# Puissance_proc.net
KiCad netlist of a schematic drawn in Altium Designer
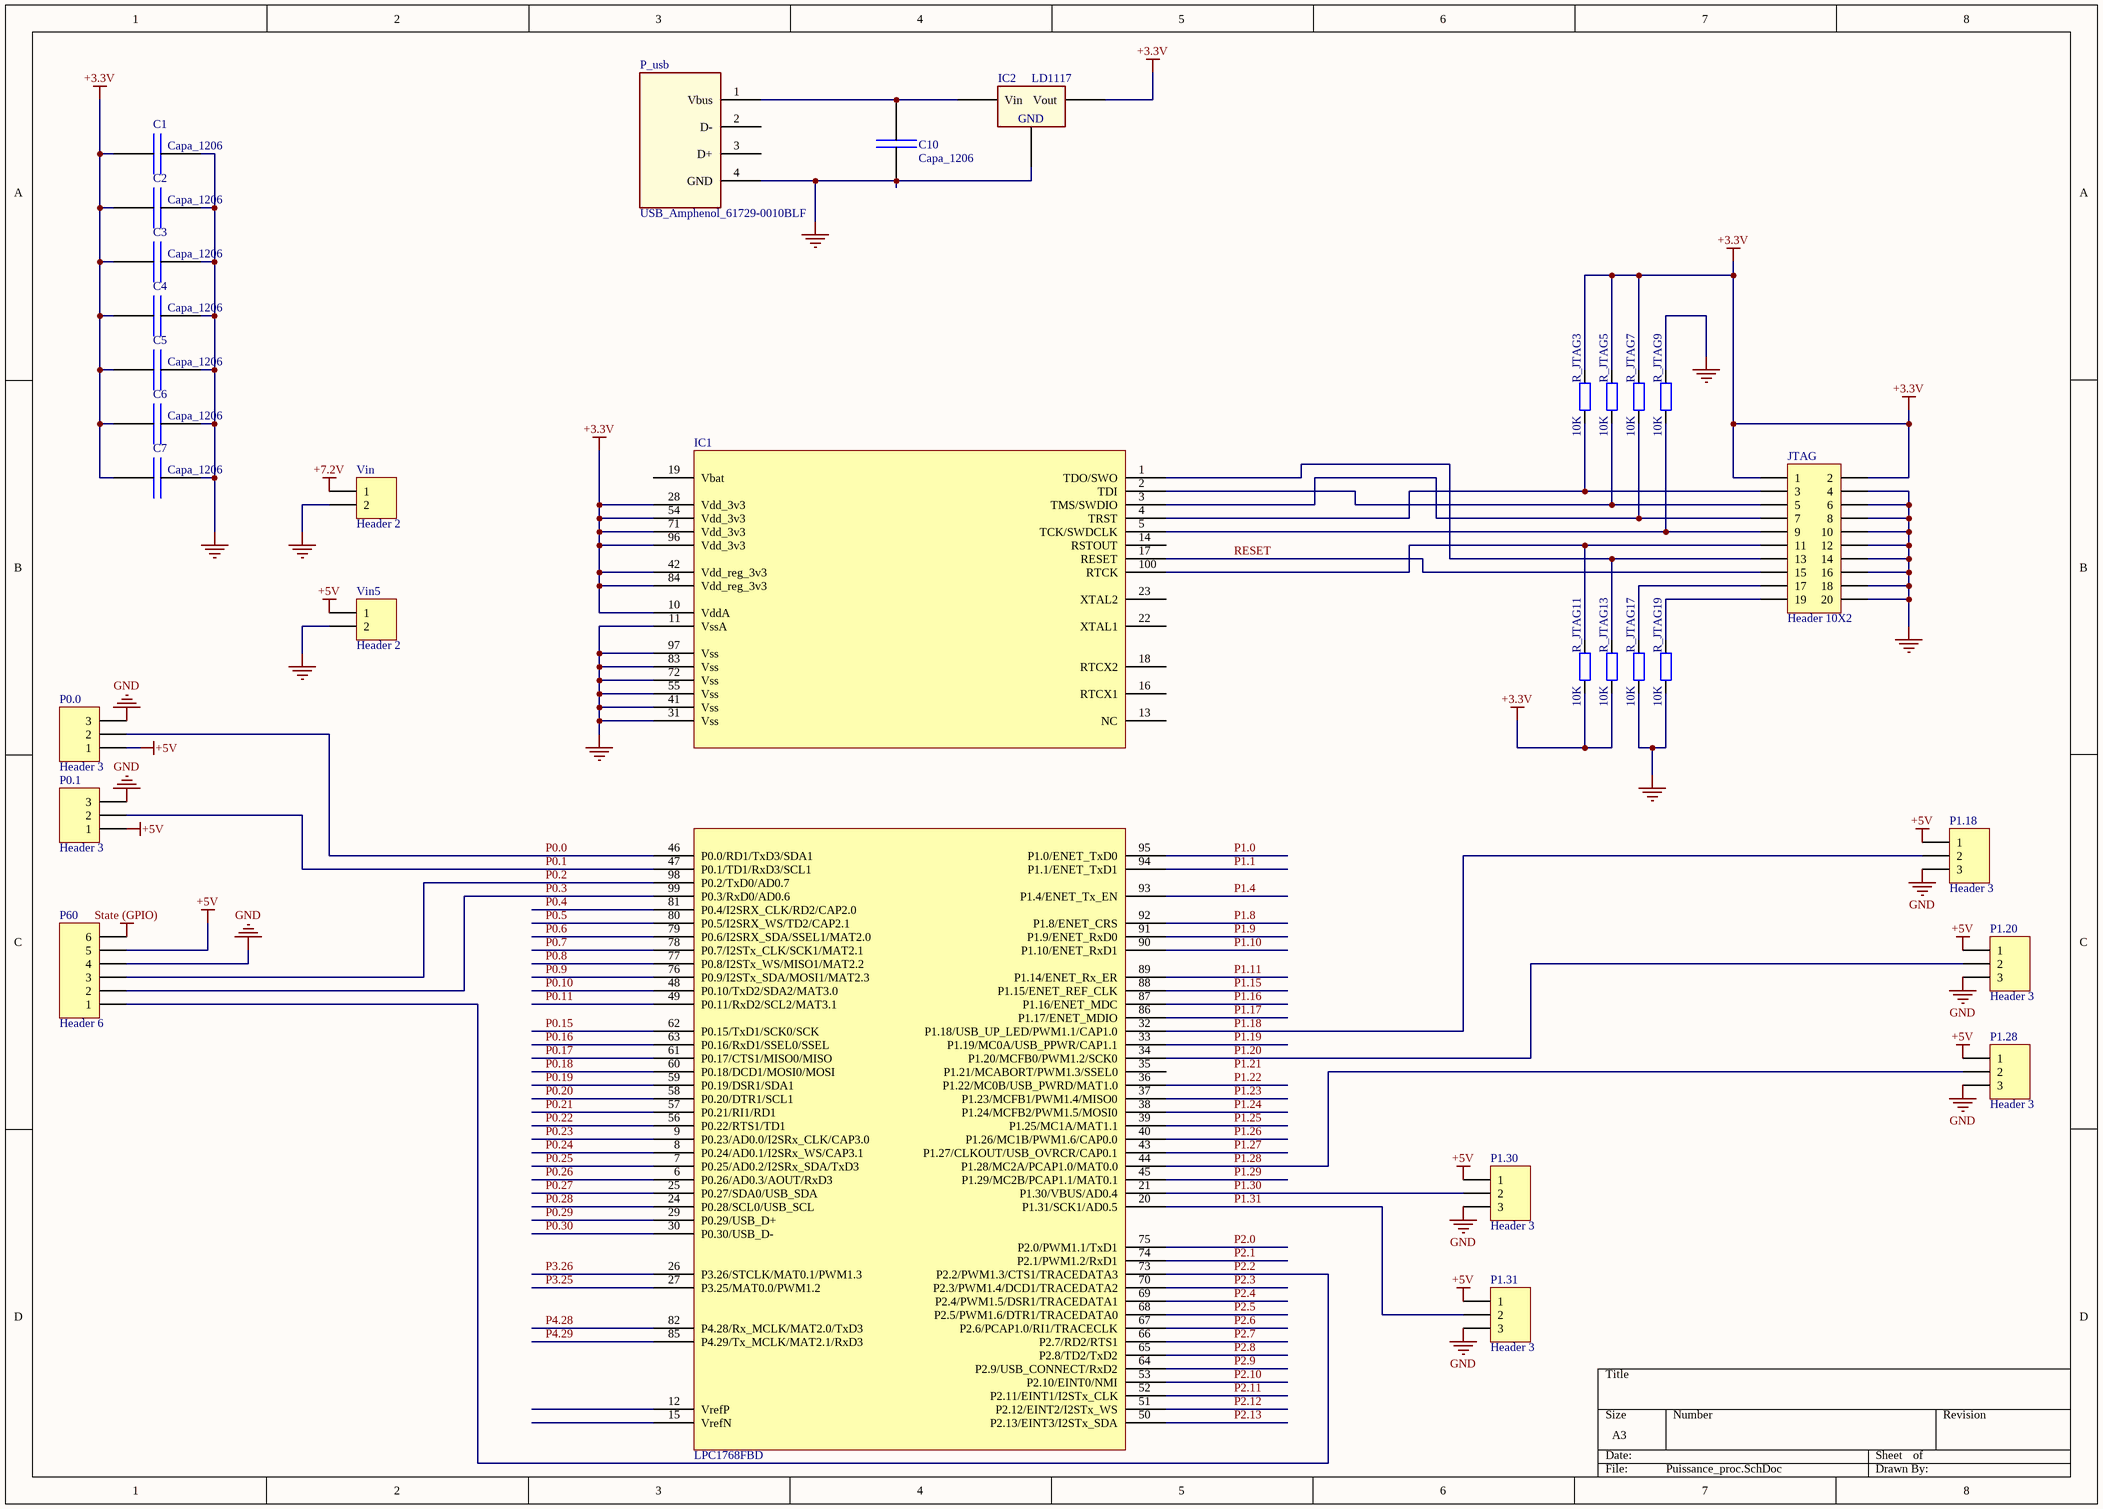
[diagram p0: Puissance_proc.SchDoc]

(export (version "E")
  (design (tool "Eeschema 10.0.6"))
  (components
    (comp (ref "C1")
      (value "Capa_1206")
      (footprint "Res_1206")
      (libsource (lib "LibEmile") (part "Capa_1206"))
    )
    (comp (ref "C2")
      (value "Capa_1206")
      (footprint "Res_1206")
      (libsource (lib "LibEmile") (part "Capa_1206"))
    )
    (comp (ref "C3")
      (value "Capa_1206")
      (footprint "Res_1206")
      (libsource (lib "LibEmile") (part "Capa_1206"))
    )
    (comp (ref "C4")
      (value "Capa_1206")
      (footprint "Res_1206")
      (libsource (lib "LibEmile") (part "Capa_1206"))
    )
    (comp (ref "C5")
      (value "Capa_1206")
      (footprint "Res_1206")
      (libsource (lib "LibEmile") (part "Capa_1206"))
    )
    (comp (ref "C6")
      (value "Capa_1206")
      (footprint "Res_1206")
      (libsource (lib "LibEmile") (part "Capa_1206"))
    )
    (comp (ref "C7")
      (value "Capa_1206")
      (footprint "Res_1206")
      (libsource (lib "LibEmile") (part "Capa_1206"))
    )
    (comp (ref "C10")
      (value "Capa_1206")
      (footprint "CC3216-1206")
      (libsource (lib "LibEmile") (part "Capa_1206"))
    )
    (comp (ref "IC1")
      (value "LPC1768FBD")
      (footprint "F-QFP14X14-G100/Z17N")
      (description "NXP Cortex M3 LPC1768")
      (libsource (lib "LibCarte_Keil_base") (part "LPC1768FBD"))
    )
    (comp (ref "IC2")
      (value "LD1117")
      (footprint "SOT-223")
      (description "PAD a Vout")
      (libsource (lib "LibCarte_Keil_base") (part "LD1117"))
    )
    (comp (ref "JTAG")
      (value "Header 10X2")
      (footprint "HDR2X10")
      (description "Header, 10-Pin, Dual row")
      (fields (field (name "PUBLISHER") "Altium Limited"))
      (libsource (lib "Miscellaneous Connectors") (part "Header 10X2"))
    )
    (comp (ref "P0.0")
      (value "Header 3")
      (footprint "HDR1X3")
      (description "Header, 3-Pin")
      (fields (field (name "PUBLISHER") "Altium Limited"))
      (libsource (lib "Miscellaneous Connectors") (part "Header 3"))
    )
    (comp (ref "P0.1")
      (value "Header 3")
      (footprint "HDR1X3")
      (description "Header, 3-Pin")
      (fields (field (name "PUBLISHER") "Altium Limited"))
      (libsource (lib "Miscellaneous Connectors") (part "Header 3"))
    )
    (comp (ref "P1.18")
      (value "Header 3")
      (footprint "HDR1X3")
      (description "Header, 3-Pin")
      (fields (field (name "PUBLISHER") "Altium Limited"))
      (libsource (lib "") (part "Header 3_1"))
    )
    (comp (ref "P1.20")
      (value "Header 3")
      (footprint "HDR1X3")
      (description "Header, 3-Pin")
      (fields (field (name "PUBLISHER") "Altium Limited"))
      (libsource (lib "") (part "Header 3_1"))
    )
    (comp (ref "P1.28")
      (value "Header 3")
      (footprint "HDR1X3")
      (description "Header, 3-Pin")
      (fields (field (name "PUBLISHER") "Altium Limited"))
      (libsource (lib "") (part "Header 3_1"))
    )
    (comp (ref "P1.30")
      (value "Header 3")
      (footprint "HDR1X3")
      (description "Header, 3-Pin")
      (fields (field (name "PUBLISHER") "Altium Limited"))
      (libsource (lib "") (part "Header 3_1"))
    )
    (comp (ref "P1.31")
      (value "Header 3")
      (footprint "HDR1X3")
      (description "Header, 3-Pin")
      (fields (field (name "PUBLISHER") "Altium Limited"))
      (libsource (lib "") (part "Header 3_1"))
    )
    (comp (ref "P60")
      (value "Header 6")
      (footprint "HDR1X6")
      (description "Header, 6-Pin")
      (fields (field (name "PUBLISHER") "Altium Limited"))
      (libsource (lib "Miscellaneous Connectors") (part "Header 6"))
    )
    (comp (ref "P_usb")
      (value "USB_Amphenol_61729-0010BLF")
      (footprint "USB_B_Amphenol_61729-0010BLF")
      (description "61729-0010BLF Farnell 1097897")
      (libsource (lib "LibCarte_Keil_base") (part "USB_Amphenol_61729-0010BLF"))
    )
    (comp (ref "R_JTAG3")
      (value "10K")
      (footprint "CR3216-1206")
      (description "Resistance")
      (fields (field (name "Comment") "Res") (field (name "PUBLISHER") "Altium Limited"))
      (libsource (lib "Gamel_Trophy_v2re6") (part "Res"))
    )
    (comp (ref "R_JTAG5")
      (value "10K")
      (footprint "CR3216-1206")
      (description "Resistance")
      (fields (field (name "Comment") "Res") (field (name "PUBLISHER") "Altium Limited"))
      (libsource (lib "Gamel_Trophy_v2re6") (part "Res"))
    )
    (comp (ref "R_JTAG7")
      (value "10K")
      (footprint "CR3216-1206")
      (description "Resistance")
      (fields (field (name "Comment") "Res") (field (name "PUBLISHER") "Altium Limited"))
      (libsource (lib "Gamel_Trophy_v2re6") (part "Res"))
    )
    (comp (ref "R_JTAG9")
      (value "10K")
      (footprint "CR3216-1206")
      (description "Resistance")
      (fields (field (name "Comment") "Res") (field (name "PUBLISHER") "Altium Limited"))
      (libsource (lib "Gamel_Trophy_v2re6") (part "Res"))
    )
    (comp (ref "R_JTAG11")
      (value "10K")
      (footprint "CR3216-1206")
      (description "Resistance")
      (fields (field (name "Comment") "Res") (field (name "PUBLISHER") "Altium Limited"))
      (libsource (lib "Gamel_Trophy_v2re6") (part "Res"))
    )
    (comp (ref "R_JTAG13")
      (value "10K")
      (footprint "CR3216-1206")
      (description "Resistance")
      (fields (field (name "Comment") "Res") (field (name "PUBLISHER") "Altium Limited"))
      (libsource (lib "Gamel_Trophy_v2re6") (part "Res"))
    )
    (comp (ref "R_JTAG17")
      (value "10K")
      (footprint "CR3216-1206")
      (description "Resistance")
      (fields (field (name "Comment") "Res") (field (name "PUBLISHER") "Altium Limited"))
      (libsource (lib "Gamel_Trophy_v2re6") (part "Res"))
    )
    (comp (ref "R_JTAG19")
      (value "10K")
      (footprint "CR3216-1206")
      (description "Resistance")
      (fields (field (name "Comment") "Res") (field (name "PUBLISHER") "Altium Limited"))
      (libsource (lib "Gamel_Trophy_v2re6") (part "Res"))
    )
    (comp (ref "Vin")
      (value "Header 2")
      (footprint "HDR1X2")
      (description "Header, 2-Pin")
      (fields (field (name "PUBLISHER") "Altium Limited"))
      (libsource (lib "Miscellaneous Connectors") (part "Header 2"))
    )
    (comp (ref "Vin5")
      (value "Header 2")
      (footprint "HDR1X2")
      (description "Header, 2-Pin")
      (fields (field (name "PUBLISHER") "Altium Limited"))
      (libsource (lib "Miscellaneous Connectors") (part "Header 2"))
    )
  )
  (nets
    (net (code "1") (name "+3.3V") (class "Default")
      (node (ref "C1") (pin "2") (pinfunction "2_2") (pintype "passive"))
      (node (ref "C2") (pin "2") (pinfunction "2_2") (pintype "passive"))
      (node (ref "C3") (pin "2") (pinfunction "2_2") (pintype "passive"))
      (node (ref "C4") (pin "2") (pinfunction "2_2") (pintype "passive"))
      (node (ref "C5") (pin "2") (pinfunction "2_2") (pintype "passive"))
      (node (ref "C6") (pin "2") (pinfunction "2_2") (pintype "passive"))
      (node (ref "C7") (pin "2") (pinfunction "2_2") (pintype "passive"))
      (node (ref "IC1") (pin "10") (pinfunction "VddA_10") (pintype "passive"))
      (node (ref "IC1") (pin "28") (pinfunction "Vdd_3v3_28") (pintype "passive"))
      (node (ref "IC1") (pin "42") (pinfunction "Vdd_reg_3v3_42") (pintype "passive"))
      (node (ref "IC1") (pin "54") (pinfunction "Vdd_3v3_54") (pintype "passive"))
      (node (ref "IC1") (pin "71") (pinfunction "Vdd_3v3_71") (pintype "passive"))
      (node (ref "IC1") (pin "84") (pinfunction "Vdd_reg_3v3_84") (pintype "passive"))
      (node (ref "IC1") (pin "96") (pinfunction "Vdd_3v3_96") (pintype "passive"))
      (node (ref "IC2") (pin "2") (pinfunction "Vout_2") (pintype "passive"))
      (node (ref "JTAG") (pin "1") (pinfunction "1_1") (pintype "passive"))
      (node (ref "JTAG") (pin "2") (pinfunction "2_2") (pintype "passive"))
      (node (ref "R_JTAG11") (pin "2") (pinfunction "2_2") (pintype "passive"))
      (node (ref "R_JTAG13") (pin "2") (pinfunction "2_2") (pintype "passive"))
      (node (ref "R_JTAG3") (pin "1") (pinfunction "1_1") (pintype "passive"))
      (node (ref "R_JTAG5") (pin "1") (pinfunction "1_1") (pintype "passive"))
      (node (ref "R_JTAG7") (pin "1") (pinfunction "1_1") (pintype "passive"))
    )
    (net (code "2") (name "+5V") (class "Default")
      (node (ref "P0.0") (pin "1") (pinfunction "1_1") (pintype "passive"))
      (node (ref "P0.1") (pin "1") (pinfunction "1_1") (pintype "passive"))
      (node (ref "P1.18") (pin "1") (pinfunction "1_1") (pintype "passive"))
      (node (ref "P1.20") (pin "1") (pinfunction "1_1") (pintype "passive"))
      (node (ref "P1.28") (pin "1") (pinfunction "1_1") (pintype "passive"))
      (node (ref "P1.30") (pin "1") (pinfunction "1_1") (pintype "passive"))
      (node (ref "P1.31") (pin "1") (pinfunction "1_1") (pintype "passive"))
      (node (ref "P60") (pin "5") (pinfunction "5_5") (pintype "passive"))
      (node (ref "Vin5") (pin "1") (pinfunction "1_1") (pintype "passive"))
    )
    (net (code "3") (name "+7.2V") (class "Default")
      (node (ref "Vin") (pin "1") (pinfunction "1_1") (pintype "passive"))
    )
    (net (code "4") (name "/P0.0") (class "Default")
      (node (ref "IC1") (pin "46") (pinfunction "P0.0/RD1/TxD3/SDA1_46") (pintype "passive"))
      (node (ref "P0.0") (pin "2") (pinfunction "2_2") (pintype "passive"))
    )
    (net (code "5") (name "/P0.1") (class "Default")
      (node (ref "IC1") (pin "47") (pinfunction "P0.1/TD1/RxD3/SCL1_47") (pintype "passive"))
      (node (ref "P0.1") (pin "2") (pinfunction "2_2") (pintype "passive"))
    )
    (net (code "6") (name "/P0.2") (class "Default")
      (node (ref "IC1") (pin "98") (pinfunction "P0.2/TxD0/AD0.7_98") (pintype "passive"))
      (node (ref "P60") (pin "3") (pinfunction "3_3") (pintype "passive"))
    )
    (net (code "7") (name "/P0.3") (class "Default")
      (node (ref "IC1") (pin "99") (pinfunction "P0.3/RxD0/AD0.6_99") (pintype "passive"))
      (node (ref "P60") (pin "2") (pinfunction "2_2") (pintype "passive"))
    )
    (net (code "8") (name "/P0.4") (class "Default")
      (node (ref "IC1") (pin "81") (pinfunction "P0.4/I2SRX_CLK/RD2/CAP2.0_81") (pintype "passive"))
    )
    (net (code "9") (name "/P0.5") (class "Default")
      (node (ref "IC1") (pin "80") (pinfunction "P0.5/I2SRX_WS/TD2/CAP2.1_80") (pintype "passive"))
    )
    (net (code "10") (name "/P0.6") (class "Default")
      (node (ref "IC1") (pin "79") (pinfunction "P0.6/I2SRX_SDA/SSEL1/MAT2.0_79") (pintype "passive"))
    )
    (net (code "11") (name "/P0.7") (class "Default")
      (node (ref "IC1") (pin "78") (pinfunction "P0.7/I2STx_CLK/SCK1/MAT2.1_78") (pintype "passive"))
    )
    (net (code "12") (name "/P0.8") (class "Default")
      (node (ref "IC1") (pin "77") (pinfunction "P0.8/I2STx_WS/MISO1/MAT2.2_77") (pintype "passive"))
    )
    (net (code "13") (name "/P0.9") (class "Default")
      (node (ref "IC1") (pin "76") (pinfunction "P0.9/I2STx_SDA/MOSI1/MAT2.3_76") (pintype "passive"))
    )
    (net (code "14") (name "/P0.10") (class "Default")
      (node (ref "IC1") (pin "48") (pinfunction "P0.10/TxD2/SDA2/MAT3.0_48") (pintype "passive"))
    )
    (net (code "15") (name "/P0.11") (class "Default")
      (node (ref "IC1") (pin "49") (pinfunction "P0.11/RxD2/SCL2/MAT3.1_49") (pintype "passive"))
    )
    (net (code "16") (name "/P0.15") (class "Default")
      (node (ref "IC1") (pin "62") (pinfunction "P0.15/TxD1/SCK0/SCK_62") (pintype "passive"))
    )
    (net (code "17") (name "/P0.16") (class "Default")
      (node (ref "IC1") (pin "63") (pinfunction "P0.16/RxD1/SSEL0/SSEL_63") (pintype "passive"))
    )
    (net (code "18") (name "/P0.17") (class "Default")
      (node (ref "IC1") (pin "61") (pinfunction "P0.17/CTS1/MISO0/MISO_61") (pintype "passive"))
    )
    (net (code "19") (name "/P0.18") (class "Default")
      (node (ref "IC1") (pin "60") (pinfunction "P0.18/DCD1/MOSI0/MOSI_60") (pintype "passive"))
    )
    (net (code "20") (name "/P0.19") (class "Default")
      (node (ref "IC1") (pin "59") (pinfunction "P0.19/DSR1/SDA1_59") (pintype "passive"))
    )
    (net (code "21") (name "/P0.20") (class "Default")
      (node (ref "IC1") (pin "58") (pinfunction "P0.20/DTR1/SCL1_58") (pintype "passive"))
    )
    (net (code "22") (name "/P0.21") (class "Default")
      (node (ref "IC1") (pin "57") (pinfunction "P0.21/RI1/RD1_57") (pintype "passive"))
    )
    (net (code "23") (name "/P0.22") (class "Default")
      (node (ref "IC1") (pin "56") (pinfunction "P0.22/RTS1/TD1_56") (pintype "passive"))
    )
    (net (code "24") (name "/P0.23") (class "Default")
      (node (ref "IC1") (pin "9") (pinfunction "P0.23/AD0.0/I2SRx_CLK/CAP3.0_9") (pintype "passive"))
    )
    (net (code "25") (name "/P0.24") (class "Default")
      (node (ref "IC1") (pin "8") (pinfunction "P0.24/AD0.1/I2SRx_WS/CAP3.1_8") (pintype "passive"))
    )
    (net (code "26") (name "/P0.25") (class "Default")
      (node (ref "IC1") (pin "7") (pinfunction "P0.25/AD0.2/I2SRx_SDA/TxD3_7") (pintype "passive"))
    )
    (net (code "27") (name "/P0.26") (class "Default")
      (node (ref "IC1") (pin "6") (pinfunction "P0.26/AD0.3/AOUT/RxD3_6") (pintype "passive"))
    )
    (net (code "28") (name "/P0.27") (class "Default")
      (node (ref "IC1") (pin "25") (pinfunction "P0.27/SDA0/USB_SDA_25") (pintype "passive"))
    )
    (net (code "29") (name "/P0.28") (class "Default")
      (node (ref "IC1") (pin "24") (pinfunction "P0.28/SCL0/USB_SCL_24") (pintype "passive"))
    )
    (net (code "30") (name "/P0.29") (class "Default")
      (node (ref "IC1") (pin "29") (pinfunction "P0.29/USB_D+_29") (pintype "passive"))
    )
    (net (code "31") (name "/P0.30") (class "Default")
      (node (ref "IC1") (pin "30") (pinfunction "P0.30/USB_D-_30") (pintype "passive"))
    )
    (net (code "32") (name "/P1.0") (class "Default")
      (node (ref "IC1") (pin "95") (pinfunction "P1.0/ENET_TxD0_95") (pintype "passive"))
    )
    (net (code "33") (name "/P1.1") (class "Default")
      (node (ref "IC1") (pin "94") (pinfunction "P1.1/ENET_TxD1_94") (pintype "passive"))
    )
    (net (code "34") (name "/P1.4") (class "Default")
      (node (ref "IC1") (pin "93") (pinfunction "P1.4/ENET_Tx_EN_93") (pintype "passive"))
    )
    (net (code "35") (name "/P1.8") (class "Default")
      (node (ref "IC1") (pin "92") (pinfunction "P1.8/ENET_CRS_92") (pintype "passive"))
    )
    (net (code "36") (name "/P1.9") (class "Default")
      (node (ref "IC1") (pin "91") (pinfunction "P1.9/ENET_RxD0_91") (pintype "passive"))
    )
    (net (code "37") (name "/P1.10") (class "Default")
      (node (ref "IC1") (pin "90") (pinfunction "P1.10/ENET_RxD1_90") (pintype "passive"))
    )
    (net (code "38") (name "/P1.11") (class "Default")
      (node (ref "IC1") (pin "89") (pinfunction "P1.14/ENET_Rx_ER_89") (pintype "passive"))
    )
    (net (code "39") (name "/P1.15") (class "Default")
      (node (ref "IC1") (pin "88") (pinfunction "P1.15/ENET_REF_CLK_88") (pintype "passive"))
    )
    (net (code "40") (name "/P1.16") (class "Default")
      (node (ref "IC1") (pin "87") (pinfunction "P1.16/ENET_MDC_87") (pintype "passive"))
    )
    (net (code "41") (name "/P1.17") (class "Default")
      (node (ref "IC1") (pin "86") (pinfunction "P1.17/ENET_MDIO_86") (pintype "passive"))
    )
    (net (code "42") (name "/P1.18") (class "Default")
      (node (ref "IC1") (pin "32") (pinfunction "P1.18/USB_UP_LED/PWM1.1/CAP1.0_32") (pintype "passive"))
      (node (ref "P1.18") (pin "2") (pinfunction "2_2") (pintype "passive"))
    )
    (net (code "43") (name "/P1.19") (class "Default")
      (node (ref "IC1") (pin "33") (pinfunction "P1.19/MC0A/USB_PPWR/CAP1.1_33") (pintype "passive"))
    )
    (net (code "44") (name "/P1.20") (class "Default")
      (node (ref "IC1") (pin "34") (pinfunction "P1.20/MCFB0/PWM1.2/SCK0_34") (pintype "passive"))
      (node (ref "P1.20") (pin "2") (pinfunction "2_2") (pintype "passive"))
    )
    (net (code "46") (name "/P1.22") (class "Default")
      (node (ref "IC1") (pin "36") (pinfunction "P1.22/MC0B/USB_PWRD/MAT1.0_36") (pintype "passive"))
    )
    (net (code "47") (name "/P1.23") (class "Default")
      (node (ref "IC1") (pin "37") (pinfunction "P1.23/MCFB1/PWM1.4/MISO0_37") (pintype "passive"))
    )
    (net (code "48") (name "/P1.24") (class "Default")
      (node (ref "IC1") (pin "38") (pinfunction "P1.24/MCFB2/PWM1.5/MOSI0_38") (pintype "passive"))
    )
    (net (code "49") (name "/P1.25") (class "Default")
      (node (ref "IC1") (pin "39") (pinfunction "P1.25/MC1A/MAT1.1_39") (pintype "passive"))
    )
    (net (code "50") (name "/P1.26") (class "Default")
      (node (ref "IC1") (pin "40") (pinfunction "P1.26/MC1B/PWM1.6/CAP0.0_40") (pintype "passive"))
    )
    (net (code "51") (name "/P1.27") (class "Default")
      (node (ref "IC1") (pin "43") (pinfunction "P1.27/CLKOUT/USB_OVRCR/CAP0.1_43") (pintype "passive"))
    )
    (net (code "52") (name "/P1.28") (class "Default")
      (node (ref "IC1") (pin "44") (pinfunction "P1.28/MC2A/PCAP1.0/MAT0.0_44") (pintype "passive"))
      (node (ref "P1.28") (pin "2") (pinfunction "2_2") (pintype "passive"))
    )
    (net (code "53") (name "/P1.29") (class "Default")
      (node (ref "IC1") (pin "45") (pinfunction "P1.29/MC2B/PCAP1.1/MAT0.1_45") (pintype "passive"))
    )
    (net (code "54") (name "/P1.30") (class "Default")
      (node (ref "IC1") (pin "21") (pinfunction "P1.30/VBUS/AD0.4_21") (pintype "passive"))
      (node (ref "P1.30") (pin "2") (pinfunction "2_2") (pintype "passive"))
    )
    (net (code "55") (name "/P1.31") (class "Default")
      (node (ref "IC1") (pin "20") (pinfunction "P1.31/SCK1/AD0.5_20") (pintype "passive"))
      (node (ref "P1.31") (pin "2") (pinfunction "2_2") (pintype "passive"))
    )
    (net (code "56") (name "/P2.0") (class "Default")
      (node (ref "IC1") (pin "75") (pinfunction "P2.0/PWM1.1/TxD1_75") (pintype "passive"))
    )
    (net (code "57") (name "/P2.1") (class "Default")
      (node (ref "IC1") (pin "74") (pinfunction "P2.1/PWM1.2/RxD1_74") (pintype "passive"))
    )
    (net (code "58") (name "/P2.2") (class "Default")
      (node (ref "IC1") (pin "73") (pinfunction "P2.2/PWM1.3/CTS1/TRACEDATA3_73") (pintype "passive"))
      (node (ref "P60") (pin "1") (pinfunction "1_1") (pintype "passive"))
    )
    (net (code "59") (name "/P2.3") (class "Default")
      (node (ref "IC1") (pin "70") (pinfunction "P2.3/PWM1.4/DCD1/TRACEDATA2_70") (pintype "passive"))
    )
    (net (code "60") (name "/P2.4") (class "Default")
      (node (ref "IC1") (pin "69") (pinfunction "P2.4/PWM1.5/DSR1/TRACEDATA1_69") (pintype "passive"))
    )
    (net (code "61") (name "/P2.5") (class "Default")
      (node (ref "IC1") (pin "68") (pinfunction "P2.5/PWM1.6/DTR1/TRACEDATA0_68") (pintype "passive"))
    )
    (net (code "62") (name "/P2.6") (class "Default")
      (node (ref "IC1") (pin "67") (pinfunction "P2.6/PCAP1.0/RI1/TRACECLK_67") (pintype "passive"))
    )
    (net (code "63") (name "/P2.7") (class "Default")
      (node (ref "IC1") (pin "66") (pinfunction "P2.7/RD2/RTS1_66") (pintype "passive"))
    )
    (net (code "64") (name "/P2.8") (class "Default")
      (node (ref "IC1") (pin "65") (pinfunction "P2.8/TD2/TxD2_65") (pintype "passive"))
    )
    (net (code "65") (name "/P2.9") (class "Default")
      (node (ref "IC1") (pin "64") (pinfunction "P2.9/USB_CONNECT/RxD2_64") (pintype "passive"))
    )
    (net (code "66") (name "/P2.10") (class "Default")
      (node (ref "IC1") (pin "53") (pinfunction "P2.10/EINT0/NMI_53") (pintype "passive"))
    )
    (net (code "67") (name "/P2.11") (class "Default")
      (node (ref "IC1") (pin "52") (pinfunction "P2.11/EINT1/I2STx_CLK_52") (pintype "passive"))
    )
    (net (code "68") (name "/P2.12") (class "Default")
      (node (ref "IC1") (pin "51") (pinfunction "P2.12/EINT2/I2STx_WS_51") (pintype "passive"))
    )
    (net (code "69") (name "/P2.13") (class "Default")
      (node (ref "IC1") (pin "50") (pinfunction "P2.13/EINT3/I2STx_SDA_50") (pintype "passive"))
    )
    (net (code "70") (name "/P3.25") (class "Default")
      (node (ref "IC1") (pin "27") (pinfunction "P3.25/MAT0.0/PWM1.2_27") (pintype "passive"))
    )
    (net (code "71") (name "/P3.26") (class "Default")
      (node (ref "IC1") (pin "26") (pinfunction "P3.26/STCLK/MAT0.1/PWM1.3_26") (pintype "passive"))
    )
    (net (code "72") (name "/P4.28") (class "Default")
      (node (ref "IC1") (pin "82") (pinfunction "P4.28/Rx_MCLK/MAT2.0/TxD3_82") (pintype "passive"))
    )
    (net (code "73") (name "/P4.29") (class "Default")
      (node (ref "IC1") (pin "85") (pinfunction "P4.29/Tx_MCLK/MAT2.1/RxD3_85") (pintype "passive"))
    )
    (net (code "74") (name "/RESET") (class "Default")
      (node (ref "IC1") (pin "17") (pinfunction "RESET_17") (pintype "passive"))
      (node (ref "JTAG") (pin "15") (pinfunction "15_15") (pintype "passive"))
    )
    (net (code "75") (name "GND") (class "Default")
      (node (ref "C1") (pin "1") (pinfunction "1_1") (pintype "passive"))
      (node (ref "C10") (pin "2") (pinfunction "2_2") (pintype "passive"))
      (node (ref "C2") (pin "1") (pinfunction "1_1") (pintype "passive"))
      (node (ref "C3") (pin "1") (pinfunction "1_1") (pintype "passive"))
      (node (ref "C4") (pin "1") (pinfunction "1_1") (pintype "passive"))
      (node (ref "C5") (pin "1") (pinfunction "1_1") (pintype "passive"))
      (node (ref "C6") (pin "1") (pinfunction "1_1") (pintype "passive"))
      (node (ref "C7") (pin "1") (pinfunction "1_1") (pintype "passive"))
      (node (ref "IC1") (pin "11") (pinfunction "VssA_11") (pintype "passive"))
      (node (ref "IC1") (pin "31") (pinfunction "Vss_31") (pintype "passive"))
      (node (ref "IC1") (pin "41") (pinfunction "Vss_41") (pintype "passive"))
      (node (ref "IC1") (pin "55") (pinfunction "Vss_55") (pintype "passive"))
      (node (ref "IC1") (pin "72") (pinfunction "Vss_72") (pintype "passive"))
      (node (ref "IC1") (pin "83") (pinfunction "Vss_83") (pintype "passive"))
      (node (ref "IC1") (pin "97") (pinfunction "Vss_97") (pintype "passive"))
      (node (ref "IC2") (pin "1") (pinfunction "GND_1") (pintype "passive"))
      (node (ref "JTAG") (pin "10") (pinfunction "10_10") (pintype "passive"))
      (node (ref "JTAG") (pin "12") (pinfunction "12_12") (pintype "passive"))
      (node (ref "JTAG") (pin "14") (pinfunction "14_14") (pintype "passive"))
      (node (ref "JTAG") (pin "16") (pinfunction "16_16") (pintype "passive"))
      (node (ref "JTAG") (pin "18") (pinfunction "18_18") (pintype "passive"))
      (node (ref "JTAG") (pin "20") (pinfunction "20_20") (pintype "passive"))
      (node (ref "JTAG") (pin "4") (pinfunction "4_4") (pintype "passive"))
      (node (ref "JTAG") (pin "6") (pinfunction "6_6") (pintype "passive"))
      (node (ref "JTAG") (pin "8") (pinfunction "8_8") (pintype "passive"))
      (node (ref "P0.0") (pin "3") (pinfunction "3_3") (pintype "passive"))
      (node (ref "P0.1") (pin "3") (pinfunction "3_3") (pintype "passive"))
      (node (ref "P1.18") (pin "3") (pinfunction "3_3") (pintype "passive"))
      (node (ref "P1.20") (pin "3") (pinfunction "3_3") (pintype "passive"))
      (node (ref "P1.28") (pin "3") (pinfunction "3_3") (pintype "passive"))
      (node (ref "P1.30") (pin "3") (pinfunction "3_3") (pintype "passive"))
      (node (ref "P1.31") (pin "3") (pinfunction "3_3") (pintype "passive"))
      (node (ref "P60") (pin "4") (pinfunction "4_4") (pintype "passive"))
      (node (ref "P_usb") (pin "4") (pinfunction "GND_4") (pintype "passive"))
      (node (ref "R_JTAG17") (pin "2") (pinfunction "2_2") (pintype "passive"))
      (node (ref "R_JTAG19") (pin "2") (pinfunction "2_2") (pintype "passive"))
      (node (ref "R_JTAG9") (pin "1") (pinfunction "1_1") (pintype "passive"))
      (node (ref "Vin") (pin "2") (pinfunction "2_2") (pintype "passive"))
      (node (ref "Vin5") (pin "2") (pinfunction "2_2") (pintype "passive"))
    )
    (net (code "76") (name "Net-(IC1-RTCK)") (class "Default")
      (node (ref "IC1") (pin "100") (pinfunction "RTCK_100") (pintype "passive"))
      (node (ref "JTAG") (pin "11") (pinfunction "11_11") (pintype "passive"))
      (node (ref "R_JTAG11") (pin "1") (pinfunction "1_1") (pintype "passive"))
    )
    (net (code "77") (name "Net-(IC1-TCK{slash}SWDCLK)") (class "Default")
      (node (ref "IC1") (pin "5") (pinfunction "TCK/SWDCLK_5") (pintype "passive"))
      (node (ref "JTAG") (pin "9") (pinfunction "9_9") (pintype "passive"))
      (node (ref "R_JTAG9") (pin "2") (pinfunction "2_2") (pintype "passive"))
    )
    (net (code "78") (name "Net-(IC1-TDI)") (class "Default")
      (node (ref "IC1") (pin "2") (pinfunction "TDI_2") (pintype "passive"))
      (node (ref "JTAG") (pin "5") (pinfunction "5_5") (pintype "passive"))
      (node (ref "R_JTAG5") (pin "2") (pinfunction "2_2") (pintype "passive"))
    )
    (net (code "79") (name "Net-(IC1-TDO{slash}SWO)") (class "Default")
      (node (ref "IC1") (pin "1") (pinfunction "TDO/SWO_1") (pintype "passive"))
      (node (ref "JTAG") (pin "13") (pinfunction "13_13") (pintype "passive"))
      (node (ref "R_JTAG13") (pin "1") (pinfunction "1_1") (pintype "passive"))
    )
    (net (code "80") (name "Net-(IC1-TMS{slash}SWDIO)") (class "Default")
      (node (ref "IC1") (pin "3") (pinfunction "TMS/SWDIO_3") (pintype "passive"))
      (node (ref "JTAG") (pin "7") (pinfunction "7_7") (pintype "passive"))
      (node (ref "R_JTAG7") (pin "2") (pinfunction "2_2") (pintype "passive"))
    )
    (net (code "81") (name "Net-(IC1-TRST)") (class "Default")
      (node (ref "IC1") (pin "4") (pinfunction "TRST_4") (pintype "passive"))
      (node (ref "JTAG") (pin "3") (pinfunction "3_3") (pintype "passive"))
      (node (ref "R_JTAG3") (pin "2") (pinfunction "2_2") (pintype "passive"))
    )
    (net (code "82") (name "Net-(IC2-Vin)") (class "Default")
      (node (ref "C10") (pin "1") (pinfunction "1_1") (pintype "passive"))
      (node (ref "IC2") (pin "3") (pinfunction "Vin_3") (pintype "passive"))
      (node (ref "P_usb") (pin "1") (pinfunction "Vbus_1") (pintype "passive"))
    )
    (net (code "83") (name "Net-(JTAG-Pad17)") (class "Default")
      (node (ref "JTAG") (pin "17") (pinfunction "17_17") (pintype "passive"))
      (node (ref "R_JTAG17") (pin "1") (pinfunction "1_1") (pintype "passive"))
    )
    (net (code "84") (name "Net-(JTAG-Pad19)") (class "Default")
      (node (ref "JTAG") (pin "19") (pinfunction "19_19") (pintype "passive"))
      (node (ref "R_JTAG19") (pin "1") (pinfunction "1_1") (pintype "passive"))
    )
    (net (code "85") (name "State (GPIO)") (class "Default")
      (node (ref "P60") (pin "6") (pinfunction "6_6") (pintype "passive"))
    )
    (net (code "86") (name "unconnected-(IC1-NC-Pad13)") (class "Default")
      (node (ref "IC1") (pin "13") (pinfunction "NC_13") (pintype "passive"))
    )
    (net (code "87") (name "unconnected-(IC1-P1.21{slash}MCABORT{slash}PWM1.3{slash}SSEL0-Pad35)") (class "Default")
      (node (ref "IC1") (pin "35") (pinfunction "P1.21/MCABORT/PWM1.3/SSEL0_35") (pintype "passive"))
    )
    (net (code "88") (name "unconnected-(IC1-RSTOUT-Pad14)") (class "Default")
      (node (ref "IC1") (pin "14") (pinfunction "RSTOUT_14") (pintype "passive"))
    )
    (net (code "89") (name "unconnected-(IC1-RTCX1-Pad16)") (class "Default")
      (node (ref "IC1") (pin "16") (pinfunction "RTCX1_16") (pintype "passive"))
    )
    (net (code "90") (name "unconnected-(IC1-RTCX2-Pad18)") (class "Default")
      (node (ref "IC1") (pin "18") (pinfunction "RTCX2_18") (pintype "passive"))
    )
    (net (code "91") (name "unconnected-(IC1-Vbat-Pad19)") (class "Default")
      (node (ref "IC1") (pin "19") (pinfunction "Vbat_19") (pintype "passive"))
    )
    (net (code "92") (name "unconnected-(IC1-VrefN-Pad15)") (class "Default")
      (node (ref "IC1") (pin "15") (pinfunction "VrefN_15") (pintype "passive"))
    )
    (net (code "93") (name "unconnected-(IC1-VrefP-Pad12)") (class "Default")
      (node (ref "IC1") (pin "12") (pinfunction "VrefP_12") (pintype "passive"))
    )
    (net (code "94") (name "unconnected-(IC1-XTAL1-Pad22)") (class "Default")
      (node (ref "IC1") (pin "22") (pinfunction "XTAL1_22") (pintype "passive"))
    )
    (net (code "95") (name "unconnected-(IC1-XTAL2-Pad23)") (class "Default")
      (node (ref "IC1") (pin "23") (pinfunction "XTAL2_23") (pintype "passive"))
    )
    (net (code "96") (name "unconnected-(P_usb-D+-Pad3)") (class "Default")
      (node (ref "P_usb") (pin "3") (pinfunction "D+_3") (pintype "passive"))
    )
    (net (code "97") (name "unconnected-(P_usb-D--Pad2)") (class "Default")
      (node (ref "P_usb") (pin "2") (pinfunction "D-_2") (pintype "passive"))
    )
  )
)
